# Lab_6.net
KiCad netlist of a schematic drawn in EAGLE
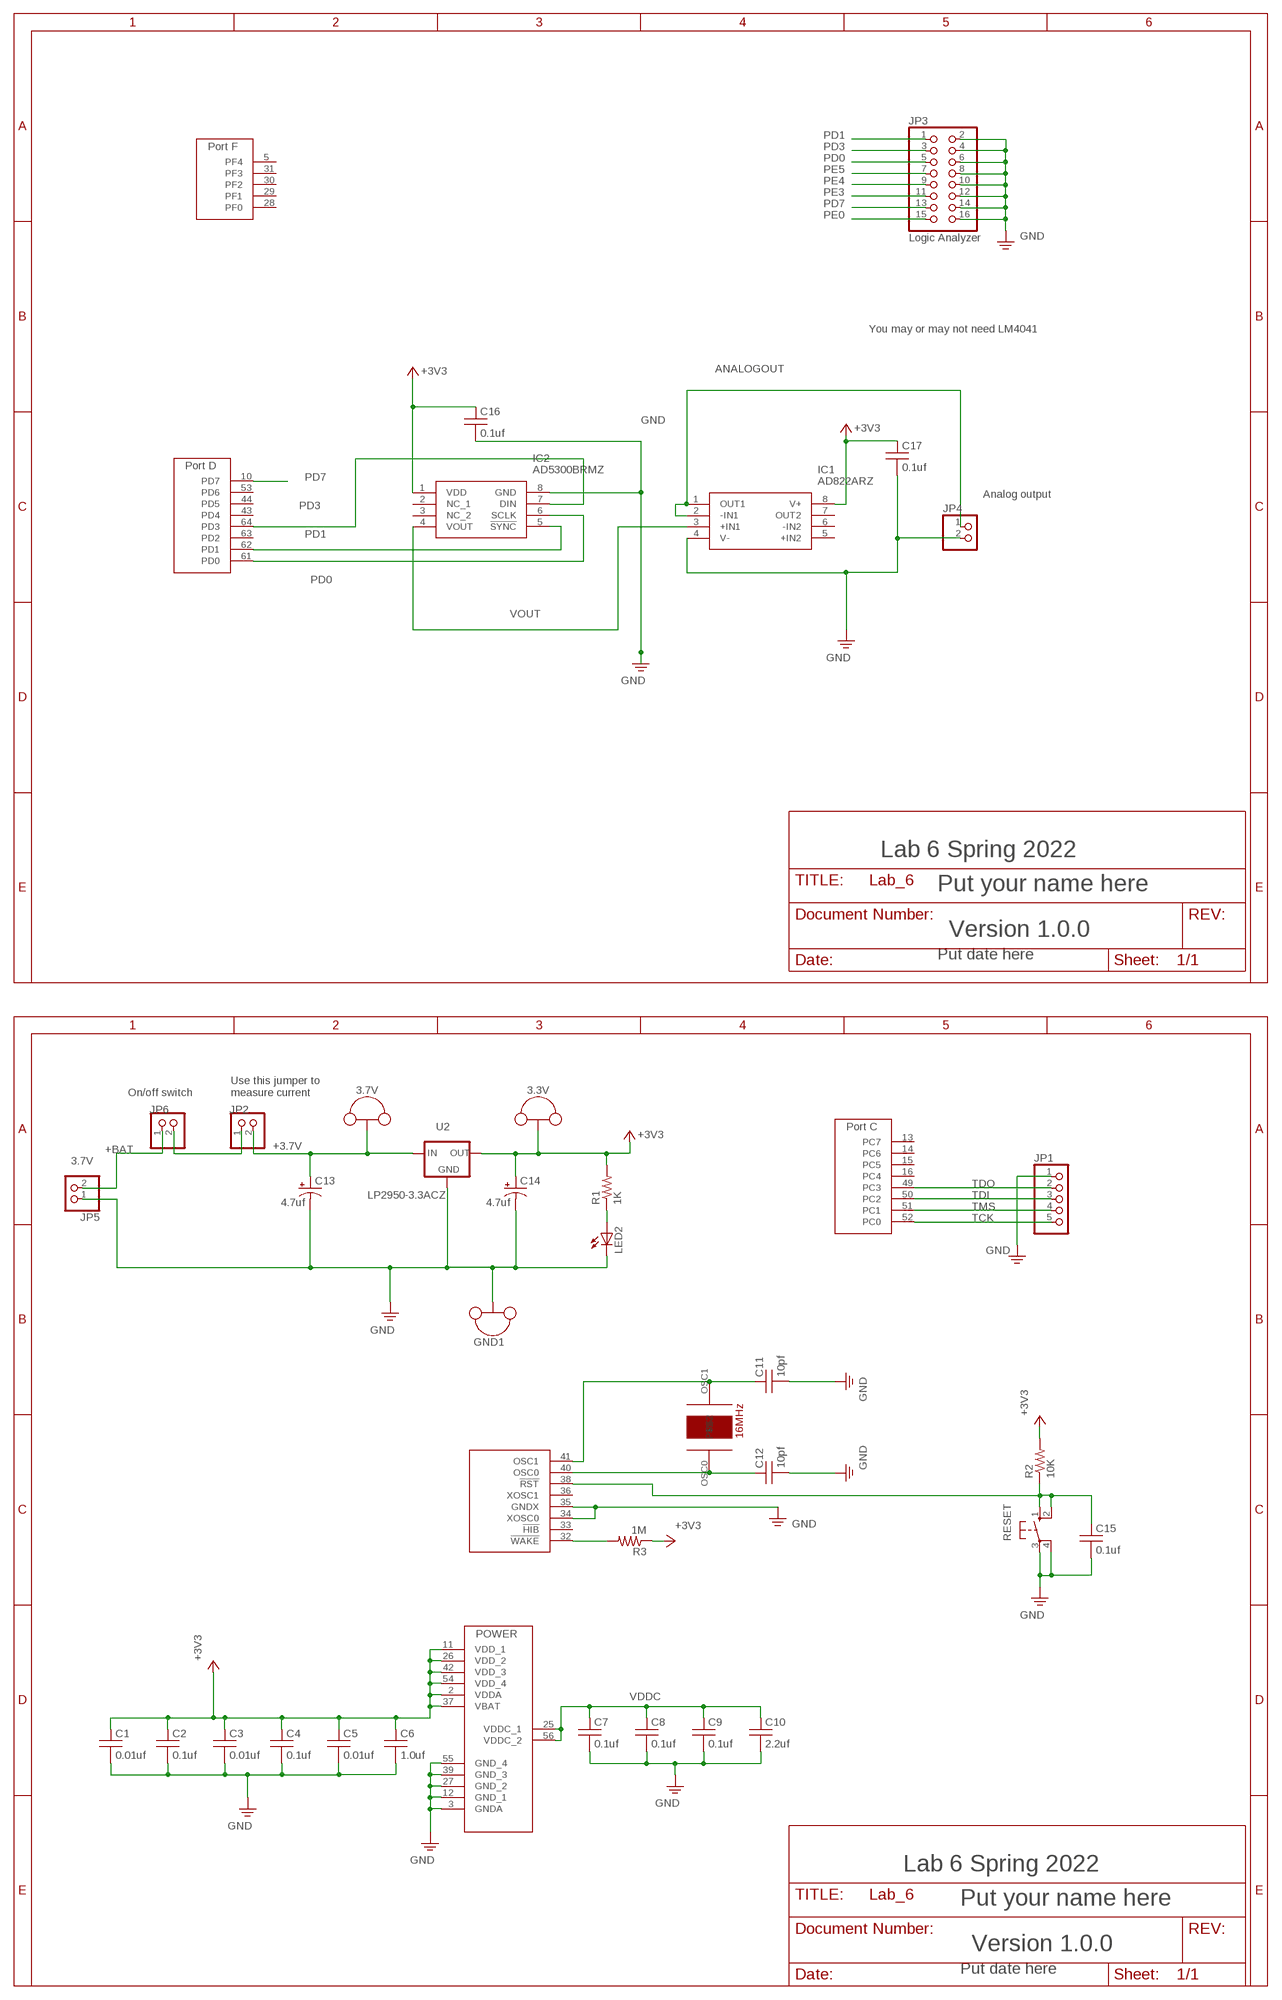
[diagram p0: schematic, sheet 1, part 1 of 2]
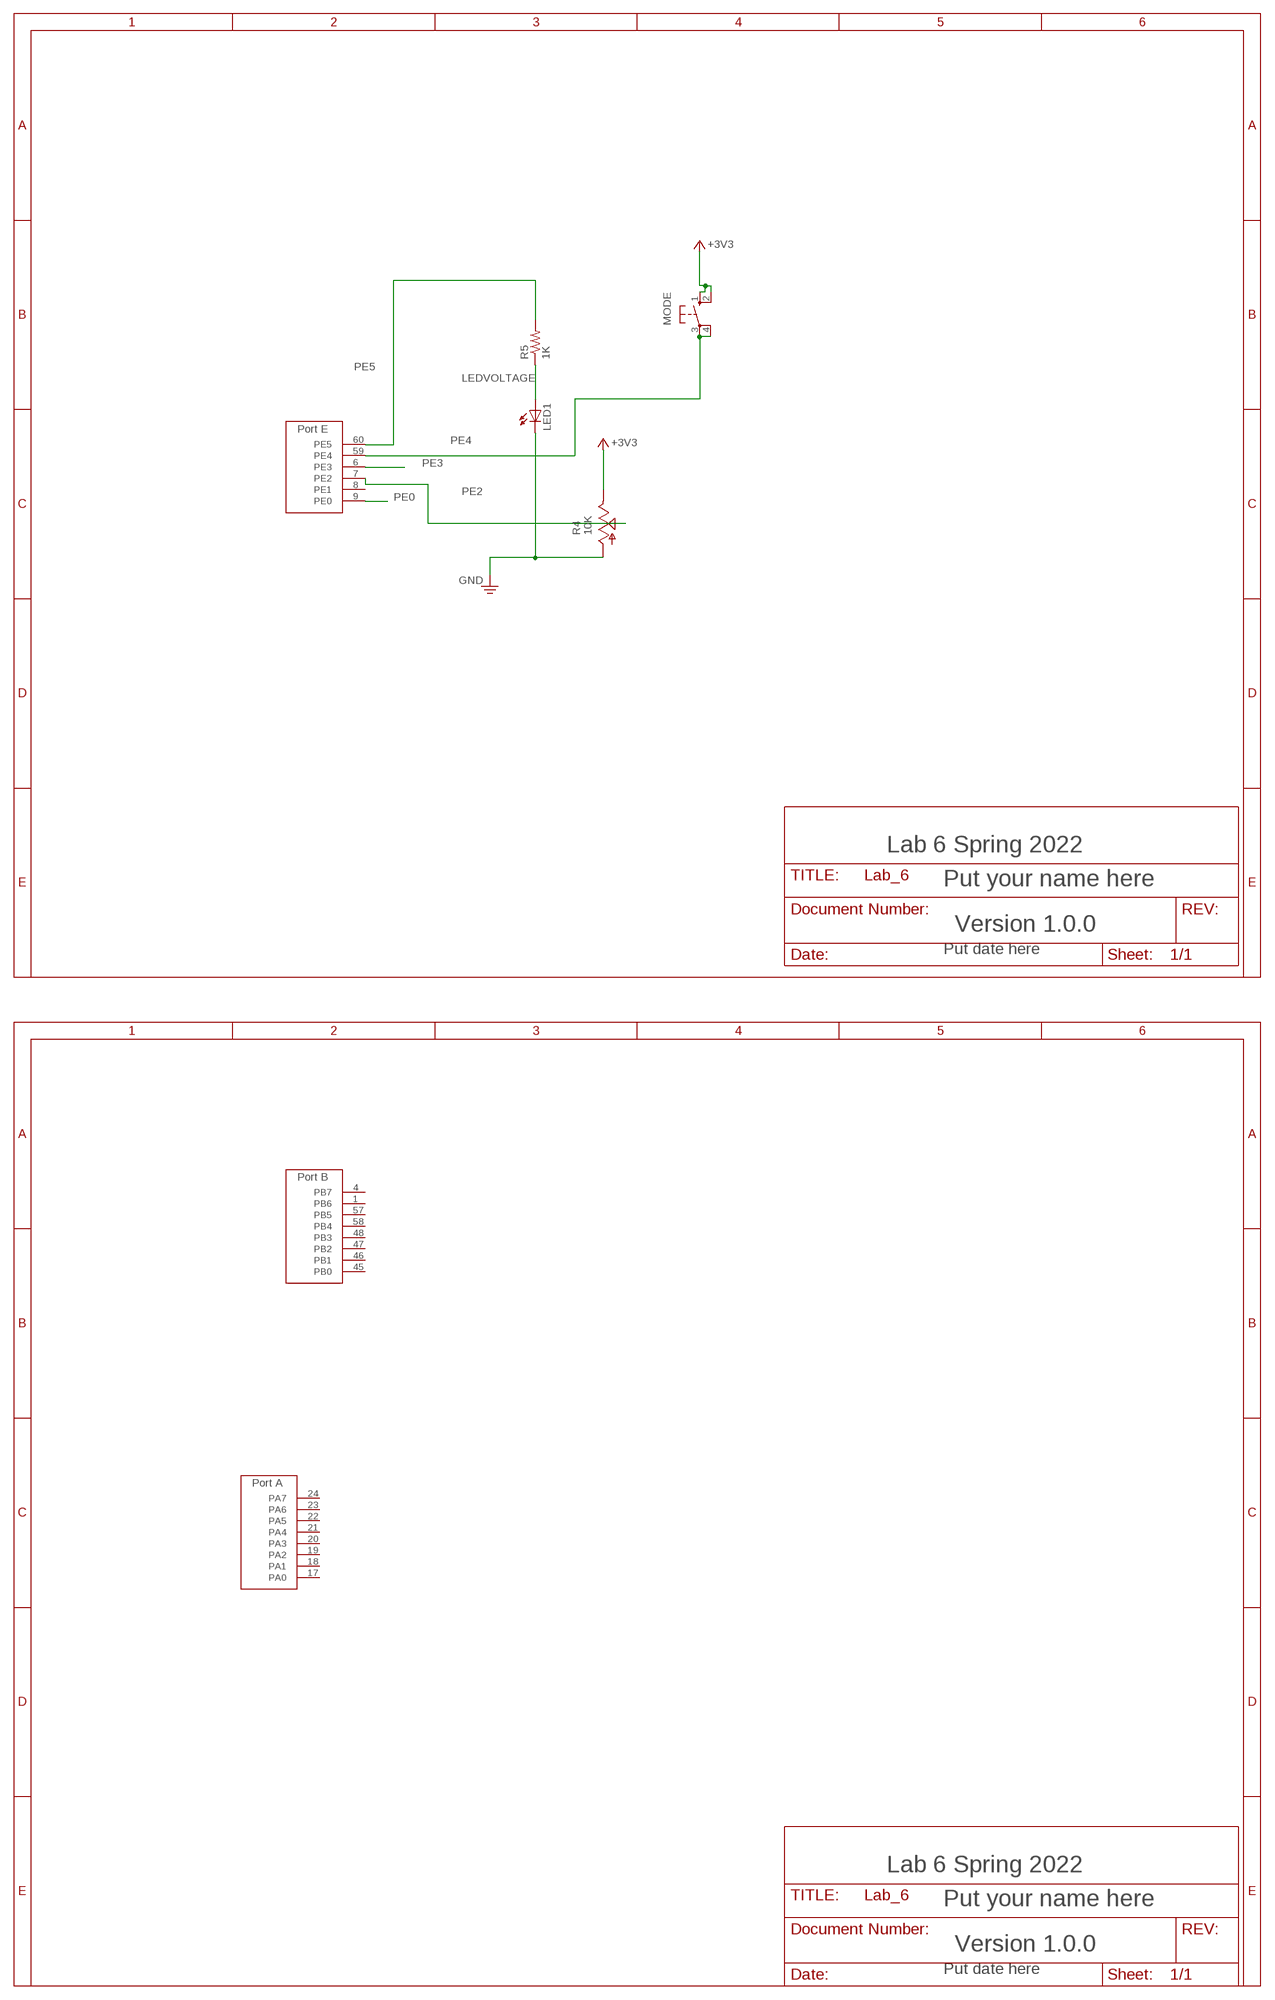
[diagram p1: schematic, sheet 1, part 2 of 2]

(export (version "E")
  (design (tool "Eeschema 10.0.6"))
  (components
    (comp (ref "3.3V")
      (value "TP_LOOP")
      (footprint "eagle-import:TP_LOOP")
      (libsource (lib "eagle-import") (part "TP_LOOP"))
    )
    (comp (ref "3.7V")
      (value "TP_LOOP")
      (footprint "eagle-import:TP_LOOP")
      (libsource (lib "eagle-import") (part "TP_LOOP"))
    )
    (comp (ref "C1")
      (value "0.01uf")
      (footprint "eagle-import:CAP100MIL")
      (libsource (lib "eagle-import") (part "CAPACITOR025-024X044"))
    )
    (comp (ref "C2")
      (value "0.1uf")
      (footprint "eagle-import:CAP100MIL")
      (libsource (lib "eagle-import") (part "CAPACITOR025-024X044"))
    )
    (comp (ref "C3")
      (value "0.01uf")
      (footprint "eagle-import:CAP100MIL")
      (libsource (lib "eagle-import") (part "CAPACITOR025-024X044"))
    )
    (comp (ref "C4")
      (value "0.1uf")
      (footprint "eagle-import:CAP100MIL")
      (libsource (lib "eagle-import") (part "CAPACITOR025-024X044"))
    )
    (comp (ref "C5")
      (value "0.01uf")
      (footprint "eagle-import:CAP100MIL")
      (libsource (lib "eagle-import") (part "CAPACITOR025-024X044"))
    )
    (comp (ref "C6")
      (value "1.0uf")
      (footprint "eagle-import:CAP100MIL")
      (libsource (lib "eagle-import") (part "CAPACITOR025-024X044"))
    )
    (comp (ref "C7")
      (value "0.1uf")
      (footprint "eagle-import:CAP100MIL")
      (libsource (lib "eagle-import") (part "CAPACITOR025-024X044"))
    )
    (comp (ref "C8")
      (value "0.1uf")
      (footprint "eagle-import:CAP100MIL")
      (libsource (lib "eagle-import") (part "CAPACITOR025-024X044"))
    )
    (comp (ref "C9")
      (value "0.1uf")
      (footprint "eagle-import:CAP100MIL")
      (libsource (lib "eagle-import") (part "CAPACITOR025-024X044"))
    )
    (comp (ref "C10")
      (value "2.2uf")
      (footprint "eagle-import:CAP100MIL")
      (libsource (lib "eagle-import") (part "CAPACITOR025-024X044"))
    )
    (comp (ref "C11")
      (value "10pf")
      (footprint "eagle-import:CAP100MIL")
      (libsource (lib "eagle-import") (part "CAPACITOR025-024X044"))
    )
    (comp (ref "C12")
      (value "10pf")
      (footprint "eagle-import:CAP100MIL")
      (libsource (lib "eagle-import") (part "CAPACITOR025-024X044"))
    )
    (comp (ref "C13")
      (value "4.7uf")
      (footprint "eagle-import:CAP200MILPOLARIZED")
      (libsource (lib "eagle-import") (part "CAPACITOR_POLARIZEDE5-6"))
    )
    (comp (ref "C14")
      (value "4.7uf")
      (footprint "eagle-import:CAP200MILPOLARIZED")
      (libsource (lib "eagle-import") (part "CAPACITOR_POLARIZEDE5-6"))
    )
    (comp (ref "C15")
      (value "0.1uf")
      (footprint "eagle-import:CAP100MIL")
      (libsource (lib "eagle-import") (part "CAPACITOR025-024X044"))
    )
    (comp (ref "C16")
      (value "0.1uf")
      (footprint "eagle-import:CAP100MIL")
      (libsource (lib "eagle-import") (part "CAPACITOR025-024X044"))
    )
    (comp (ref "C17")
      (value "0.1uf")
      (footprint "eagle-import:CAP100MIL")
      (libsource (lib "eagle-import") (part "CAPACITOR025-024X044"))
    )
    (comp (ref "GND1")
      (value "TP_LOOP")
      (footprint "eagle-import:TP_LOOP")
      (libsource (lib "eagle-import") (part "TP_LOOP"))
    )
    (comp (ref "IC1")
      (value "AD822ARZ")
      (footprint "eagle-import:SOIC127P600X175-8N")
      (fields (field (name "MOUSER2_PART_NUMBER") "584-AD822ARZ"))
      (libsource (lib "eagle-import") (part "AD822ARZ"))
    )
    (comp (ref "IC2")
      (value "AD5300BRMZ")
      (footprint "eagle-import:SOP65P490X110-8N")
      (fields (field (name "MOUSER_PART_NUMBER") "584-AD5300BRMZ"))
      (libsource (lib "eagle-import") (part "AD5300BRMZ"))
    )
    (comp (ref "JP1")
      (value "PINHD-1X5")
      (footprint "eagle-import:1X05")
      (libsource (lib "eagle-import") (part "PINHD-1X5"))
    )
    (comp (ref "JP2")
      (value "PINHD-1X2")
      (footprint "eagle-import:1X02")
      (libsource (lib "eagle-import") (part "PINHD-1X2"))
    )
    (comp (ref "JP3")
      (value "Logic Analyzer")
      (footprint "eagle-import:2X08")
      (libsource (lib "eagle-import") (part "PINHD-2X8"))
    )
    (comp (ref "JP4")
      (value "PINHD-1X2")
      (footprint "eagle-import:1X02")
      (libsource (lib "eagle-import") (part "PINHD-1X2"))
    )
    (comp (ref "JP5")
      (value "PINHD-1X2")
      (footprint "eagle-import:1X02")
      (libsource (lib "eagle-import") (part "PINHD-1X2"))
    )
    (comp (ref "JP6")
      (value "PINHD-1X2")
      (footprint "eagle-import:1X02")
      (libsource (lib "eagle-import") (part "PINHD-1X2"))
    )
    (comp (ref "LED1")
      (value "LED3MM")
      (footprint "eagle-import:LED3MM")
      (libsource (lib "eagle-import") (part "LED3MM"))
    )
    (comp (ref "LED2")
      (value "LED3MM")
      (footprint "eagle-import:LED3MM")
      (libsource (lib "eagle-import") (part "LED3MM"))
    )
    (comp (ref "MODE")
      (value "B3F-1052")
      (footprint "eagle-import:B3F-10XX")
      (fields (field (name "MPN") "B3F-1000"))
      (libsource (lib "eagle-import") (part "B3F-1052"))
    )
    (comp (ref "R1")
      (value "1K")
      (footprint "eagle-import:RES200MIL")
      (libsource (lib "eagle-import") (part "RESISTOR0204/5"))
    )
    (comp (ref "R2")
      (value "10K")
      (footprint "eagle-import:RES200MIL")
      (libsource (lib "eagle-import") (part "RESISTOR0204/5"))
    )
    (comp (ref "R3")
      (value "1M")
      (footprint "eagle-import:RES200MIL")
      (libsource (lib "eagle-import") (part "RESISTOR0204/5"))
    )
    (comp (ref "R4")
      (value "10K")
      (footprint "eagle-import:PTA2043")
      (libsource (lib "eagle-import") (part "POTENTIOMETER_PTA2043B25U"))
    )
    (comp (ref "R5")
      (value "1K")
      (footprint "eagle-import:RES200MIL")
      (libsource (lib "eagle-import") (part "RESISTOR0204/5"))
    )
    (comp (ref "RESET")
      (value "B3F-1052")
      (footprint "eagle-import:B3F-10XX")
      (fields (field (name "MPN") "B3F-1000"))
      (libsource (lib "eagle-import") (part "B3F-1052"))
    )
    (comp (ref "U1")
      (value "TM4C123GH6PM")
      (footprint "eagle-import:QFP50P1200X1200X160-64N")
      (libsource (lib "eagle-import") (part "TM4C123GH6PM"))
    )
    (comp (ref "U2")
      (value "LP2950-3.3ACZ")
      (footprint "eagle-import:TO92")
      (libsource (lib "eagle-import") (part "LP2950ACZ-3.3"))
    )
    (comp (ref "Y1")
      (value "16MHZ_CRYSTAL")
      (footprint "eagle-import:16MHZ_CRYSTAL")
      (libsource (lib "eagle-import") (part "16MHZ_CRYSTAL"))
    )
  )
  (nets
    (net (code "1") (name "+3V3") (class "Default")
      (node (ref "3.3V") (pin "P$1") (pinfunction "TP_P$1") (pintype "bidirectional"))
      (node (ref "3.3V") (pin "P$2") (pinfunction "TP_P$2") (pintype "bidirectional"))
      (node (ref "C1") (pin "1") (pinfunction "1_1") (pintype "passive"))
      (node (ref "C14") (pin "+") (pinfunction "+_+") (pintype "passive"))
      (node (ref "C16") (pin "1") (pinfunction "1_1") (pintype "passive"))
      (node (ref "C17") (pin "1") (pinfunction "1_1") (pintype "passive"))
      (node (ref "C2") (pin "1") (pinfunction "1_1") (pintype "passive"))
      (node (ref "C3") (pin "1") (pinfunction "1_1") (pintype "passive"))
      (node (ref "C4") (pin "1") (pinfunction "1_1") (pintype "passive"))
      (node (ref "C5") (pin "1") (pinfunction "1_1") (pintype "passive"))
      (node (ref "C6") (pin "1") (pinfunction "1_1") (pintype "passive"))
      (node (ref "IC1") (pin "8") (pinfunction "V+_8") (pintype "bidirectional"))
      (node (ref "IC2") (pin "1") (pinfunction "VDD_1") (pintype "bidirectional"))
      (node (ref "MODE") (pin "1") (pinfunction "S_1") (pintype "passive"))
      (node (ref "MODE") (pin "2") (pinfunction "S1_2") (pintype "passive"))
      (node (ref "R1") (pin "2") (pinfunction "2_2") (pintype "passive"))
      (node (ref "R2") (pin "2") (pinfunction "2_2") (pintype "passive"))
      (node (ref "R3") (pin "1") (pinfunction "1_1") (pintype "passive"))
      (node (ref "R4") (pin "1") (pinfunction "E_1") (pintype "passive"))
      (node (ref "U1") (pin "11") (pinfunction "VDD_1_11") (pintype "bidirectional"))
      (node (ref "U1") (pin "2") (pinfunction "VDDA_2") (pintype "bidirectional"))
      (node (ref "U1") (pin "26") (pinfunction "VDD_2_26") (pintype "bidirectional"))
      (node (ref "U1") (pin "37") (pinfunction "VBAT_37") (pintype "bidirectional"))
      (node (ref "U1") (pin "42") (pinfunction "VDD_3_42") (pintype "bidirectional"))
      (node (ref "U1") (pin "54") (pinfunction "VDD_4_54") (pintype "bidirectional"))
      (node (ref "U2") (pin "1") (pinfunction "OUT_1") (pintype "passive"))
    )
    (net (code "2") (name "/+3.7V") (class "Default")
      (node (ref "3.7V") (pin "P$1") (pinfunction "TP_P$1") (pintype "bidirectional"))
      (node (ref "3.7V") (pin "P$2") (pinfunction "TP_P$2") (pintype "bidirectional"))
      (node (ref "C13") (pin "+") (pinfunction "+_+") (pintype "passive"))
      (node (ref "JP2") (pin "2") (pinfunction "2_2") (pintype "passive"))
      (node (ref "U2") (pin "3") (pinfunction "IN_3") (pintype "input"))
    )
    (net (code "3") (name "/+BAT") (class "Default")
      (node (ref "JP5") (pin "2") (pinfunction "2_2") (pintype "passive"))
      (node (ref "JP6") (pin "1") (pinfunction "1_1") (pintype "passive"))
    )
    (net (code "4") (name "/ANALOGOUT") (class "Default")
      (node (ref "IC1") (pin "1") (pinfunction "OUT1_1") (pintype "bidirectional"))
      (node (ref "IC1") (pin "2") (pinfunction "-IN1_2") (pintype "bidirectional"))
      (node (ref "JP4") (pin "1") (pinfunction "1_1") (pintype "passive"))
    )
    (net (code "5") (name "/LEDVOLTAGE") (class "Default")
      (node (ref "LED1") (pin "A") (pinfunction "A_A") (pintype "passive"))
      (node (ref "R5") (pin "1") (pinfunction "1_1") (pintype "passive"))
    )
    (net (code "6") (name "/PD0") (class "Default")
      (node (ref "IC2") (pin "6") (pinfunction "SCLK_6") (pintype "bidirectional"))
      (node (ref "JP3") (pin "5") (pinfunction "5_5") (pintype "passive"))
      (node (ref "U1") (pin "61") (pinfunction "PD0_61") (pintype "bidirectional"))
    )
    (net (code "7") (name "/PD1") (class "Default")
      (node (ref "IC2") (pin "5") (pinfunction "~{SYNC}_5") (pintype "bidirectional"))
      (node (ref "JP3") (pin "1") (pinfunction "1_1") (pintype "passive"))
      (node (ref "U1") (pin "62") (pinfunction "PD1_62") (pintype "bidirectional"))
    )
    (net (code "8") (name "/PD3") (class "Default")
      (node (ref "IC2") (pin "7") (pinfunction "DIN_7") (pintype "bidirectional"))
      (node (ref "JP3") (pin "3") (pinfunction "3_3") (pintype "passive"))
      (node (ref "U1") (pin "64") (pinfunction "PD3_64") (pintype "bidirectional"))
    )
    (net (code "9") (name "/PD7") (class "Default")
      (node (ref "JP3") (pin "13") (pinfunction "13_13") (pintype "passive"))
      (node (ref "U1") (pin "10") (pinfunction "PD7_10") (pintype "bidirectional"))
    )
    (net (code "10") (name "/PE0") (class "Default")
      (node (ref "JP3") (pin "15") (pinfunction "15_15") (pintype "passive"))
      (node (ref "U1") (pin "9") (pinfunction "PE0_9") (pintype "bidirectional"))
    )
    (net (code "11") (name "/PE2") (class "Default")
      (node (ref "R4") (pin "2") (pinfunction "S_2") (pintype "passive"))
      (node (ref "U1") (pin "7") (pinfunction "PE2_7") (pintype "bidirectional"))
    )
    (net (code "12") (name "/PE3") (class "Default")
      (node (ref "JP3") (pin "11") (pinfunction "11_11") (pintype "passive"))
      (node (ref "U1") (pin "6") (pinfunction "PE3_6") (pintype "bidirectional"))
    )
    (net (code "13") (name "/PE4") (class "Default")
      (node (ref "JP3") (pin "9") (pinfunction "9_9") (pintype "passive"))
      (node (ref "MODE") (pin "3") (pinfunction "P_3") (pintype "passive"))
      (node (ref "MODE") (pin "4") (pinfunction "P1_4") (pintype "passive"))
      (node (ref "U1") (pin "59") (pinfunction "PE4_59") (pintype "bidirectional"))
    )
    (net (code "14") (name "/PE5") (class "Default")
      (node (ref "JP3") (pin "7") (pinfunction "7_7") (pintype "passive"))
      (node (ref "R5") (pin "2") (pinfunction "2_2") (pintype "passive"))
      (node (ref "U1") (pin "60") (pinfunction "PE5_60") (pintype "bidirectional"))
    )
    (net (code "15") (name "/TCK") (class "Default")
      (node (ref "JP1") (pin "5") (pinfunction "5_5") (pintype "passive"))
      (node (ref "U1") (pin "52") (pinfunction "PC0_52") (pintype "bidirectional"))
    )
    (net (code "16") (name "/TDI") (class "Default")
      (node (ref "JP1") (pin "3") (pinfunction "3_3") (pintype "passive"))
      (node (ref "U1") (pin "50") (pinfunction "PC2_50") (pintype "bidirectional"))
    )
    (net (code "17") (name "/TDO") (class "Default")
      (node (ref "JP1") (pin "2") (pinfunction "2_2") (pintype "passive"))
      (node (ref "U1") (pin "49") (pinfunction "PC3_49") (pintype "bidirectional"))
    )
    (net (code "18") (name "/TMS") (class "Default")
      (node (ref "JP1") (pin "4") (pinfunction "4_4") (pintype "passive"))
      (node (ref "U1") (pin "51") (pinfunction "PC1_51") (pintype "bidirectional"))
    )
    (net (code "19") (name "/VDDC") (class "Default")
      (node (ref "C10") (pin "1") (pinfunction "1_1") (pintype "passive"))
      (node (ref "C7") (pin "1") (pinfunction "1_1") (pintype "passive"))
      (node (ref "C8") (pin "1") (pinfunction "1_1") (pintype "passive"))
      (node (ref "C9") (pin "1") (pinfunction "1_1") (pintype "passive"))
      (node (ref "U1") (pin "25") (pinfunction "VDDC_1_25") (pintype "bidirectional"))
      (node (ref "U1") (pin "56") (pinfunction "VDDC_2_56") (pintype "bidirectional"))
    )
    (net (code "20") (name "/VOUT") (class "Default")
      (node (ref "IC1") (pin "3") (pinfunction "+IN1_3") (pintype "bidirectional"))
      (node (ref "IC2") (pin "4") (pinfunction "VOUT_4") (pintype "bidirectional"))
    )
    (net (code "21") (name "GND") (class "Default")
      (node (ref "C1") (pin "2") (pinfunction "2_2") (pintype "passive"))
      (node (ref "C10") (pin "2") (pinfunction "2_2") (pintype "passive"))
      (node (ref "C11") (pin "2") (pinfunction "2_2") (pintype "passive"))
      (node (ref "C12") (pin "2") (pinfunction "2_2") (pintype "passive"))
      (node (ref "C13") (pin "-") (pinfunction "-_-") (pintype "passive"))
      (node (ref "C14") (pin "-") (pinfunction "-_-") (pintype "passive"))
      (node (ref "C15") (pin "2") (pinfunction "2_2") (pintype "passive"))
      (node (ref "C16") (pin "2") (pinfunction "2_2") (pintype "passive"))
      (node (ref "C17") (pin "2") (pinfunction "2_2") (pintype "passive"))
      (node (ref "C2") (pin "2") (pinfunction "2_2") (pintype "passive"))
      (node (ref "C3") (pin "2") (pinfunction "2_2") (pintype "passive"))
      (node (ref "C4") (pin "2") (pinfunction "2_2") (pintype "passive"))
      (node (ref "C5") (pin "2") (pinfunction "2_2") (pintype "passive"))
      (node (ref "C6") (pin "2") (pinfunction "2_2") (pintype "passive"))
      (node (ref "C7") (pin "2") (pinfunction "2_2") (pintype "passive"))
      (node (ref "C8") (pin "2") (pinfunction "2_2") (pintype "passive"))
      (node (ref "C9") (pin "2") (pinfunction "2_2") (pintype "passive"))
      (node (ref "GND1") (pin "P$1") (pinfunction "TP_P$1") (pintype "bidirectional"))
      (node (ref "GND1") (pin "P$2") (pinfunction "TP_P$2") (pintype "bidirectional"))
      (node (ref "IC1") (pin "4") (pinfunction "V-_4") (pintype "bidirectional"))
      (node (ref "IC2") (pin "8") (pinfunction "GND_8") (pintype "bidirectional"))
      (node (ref "JP1") (pin "1") (pinfunction "1_1") (pintype "passive"))
      (node (ref "JP3") (pin "10") (pinfunction "10_10") (pintype "passive"))
      (node (ref "JP3") (pin "12") (pinfunction "12_12") (pintype "passive"))
      (node (ref "JP3") (pin "14") (pinfunction "14_14") (pintype "passive"))
      (node (ref "JP3") (pin "16") (pinfunction "16_16") (pintype "passive"))
      (node (ref "JP3") (pin "2") (pinfunction "2_2") (pintype "passive"))
      (node (ref "JP3") (pin "4") (pinfunction "4_4") (pintype "passive"))
      (node (ref "JP3") (pin "6") (pinfunction "6_6") (pintype "passive"))
      (node (ref "JP3") (pin "8") (pinfunction "8_8") (pintype "passive"))
      (node (ref "JP4") (pin "2") (pinfunction "2_2") (pintype "passive"))
      (node (ref "JP5") (pin "1") (pinfunction "1_1") (pintype "passive"))
      (node (ref "LED1") (pin "K") (pinfunction "C_K") (pintype "passive"))
      (node (ref "LED2") (pin "K") (pinfunction "C_K") (pintype "passive"))
      (node (ref "R4") (pin "3") (pinfunction "A_3") (pintype "passive"))
      (node (ref "RESET") (pin "3") (pinfunction "P_3") (pintype "passive"))
      (node (ref "RESET") (pin "4") (pinfunction "P1_4") (pintype "passive"))
      (node (ref "U1") (pin "12") (pinfunction "GND_1_12") (pintype "bidirectional"))
      (node (ref "U1") (pin "27") (pinfunction "GND_2_27") (pintype "bidirectional"))
      (node (ref "U1") (pin "3") (pinfunction "GNDA_3") (pintype "bidirectional"))
      (node (ref "U1") (pin "34") (pinfunction "XOSC0_34") (pintype "bidirectional"))
      (node (ref "U1") (pin "35") (pinfunction "GNDX_35") (pintype "bidirectional"))
      (node (ref "U1") (pin "39") (pinfunction "GND_3_39") (pintype "bidirectional"))
      (node (ref "U1") (pin "55") (pinfunction "GND_4_55") (pintype "bidirectional"))
      (node (ref "U2") (pin "2") (pinfunction "GND_2") (pintype "input"))
    )
    (net (code "22") (name "Net-(JP2-Pad1)") (class "Default")
      (node (ref "JP2") (pin "1") (pinfunction "1_1") (pintype "passive"))
      (node (ref "JP6") (pin "2") (pinfunction "2_2") (pintype "passive"))
    )
    (net (code "23") (name "Net-(LED2-PadA)") (class "Default")
      (node (ref "LED2") (pin "A") (pinfunction "A_A") (pintype "passive"))
      (node (ref "R1") (pin "1") (pinfunction "1_1") (pintype "passive"))
    )
    (net (code "24") (name "Net-(RESET-S)") (class "Default")
      (node (ref "C15") (pin "1") (pinfunction "1_1") (pintype "passive"))
      (node (ref "R2") (pin "1") (pinfunction "1_1") (pintype "passive"))
      (node (ref "RESET") (pin "1") (pinfunction "S_1") (pintype "passive"))
      (node (ref "RESET") (pin "2") (pinfunction "S1_2") (pintype "passive"))
      (node (ref "U1") (pin "38") (pinfunction "~{RST}_38") (pintype "bidirectional"))
    )
    (net (code "25") (name "Net-(U1G-OSC0)") (class "Default")
      (node (ref "C12") (pin "1") (pinfunction "1_1") (pintype "passive"))
      (node (ref "U1") (pin "40") (pinfunction "OSC0_40") (pintype "bidirectional"))
      (node (ref "Y1") (pin "OSC0") (pinfunction "P$1_OSC0") (pintype "bidirectional"))
    )
    (net (code "26") (name "Net-(U1G-OSC1)") (class "Default")
      (node (ref "C11") (pin "1") (pinfunction "1_1") (pintype "passive"))
      (node (ref "U1") (pin "41") (pinfunction "OSC1_41") (pintype "bidirectional"))
      (node (ref "Y1") (pin "OSC1") (pinfunction "P$2_OSC1") (pintype "bidirectional"))
    )
    (net (code "27") (name "Net-(U1G-~{WAKE})") (class "Default")
      (node (ref "R3") (pin "2") (pinfunction "2_2") (pintype "passive"))
      (node (ref "U1") (pin "32") (pinfunction "~{WAKE}_32") (pintype "bidirectional"))
    )
    (net (code "28") (name "unconnected-(IC1-+IN2-Pad5)") (class "Default")
      (node (ref "IC1") (pin "5") (pinfunction "+IN2_5") (pintype "bidirectional"))
    )
    (net (code "29") (name "unconnected-(IC1--IN2-Pad6)") (class "Default")
      (node (ref "IC1") (pin "6") (pinfunction "-IN2_6") (pintype "bidirectional"))
    )
    (net (code "30") (name "unconnected-(IC1-OUT2-Pad7)") (class "Default")
      (node (ref "IC1") (pin "7") (pinfunction "OUT2_7") (pintype "bidirectional"))
    )
    (net (code "31") (name "unconnected-(IC2-NC_1-Pad2)") (class "Default")
      (node (ref "IC2") (pin "2") (pinfunction "NC_1_2") (pintype "bidirectional"))
    )
    (net (code "32") (name "unconnected-(IC2-NC_2-Pad3)") (class "Default")
      (node (ref "IC2") (pin "3") (pinfunction "NC_2_3") (pintype "bidirectional"))
    )
    (net (code "33") (name "unconnected-(U1A-PA0-Pad17)") (class "Default")
      (node (ref "U1") (pin "17") (pinfunction "PA0_17") (pintype "bidirectional"))
    )
    (net (code "34") (name "unconnected-(U1A-PA1-Pad18)") (class "Default")
      (node (ref "U1") (pin "18") (pinfunction "PA1_18") (pintype "bidirectional"))
    )
    (net (code "35") (name "unconnected-(U1A-PA2-Pad19)") (class "Default")
      (node (ref "U1") (pin "19") (pinfunction "PA2_19") (pintype "bidirectional"))
    )
    (net (code "36") (name "unconnected-(U1A-PA3-Pad20)") (class "Default")
      (node (ref "U1") (pin "20") (pinfunction "PA3_20") (pintype "bidirectional"))
    )
    (net (code "37") (name "unconnected-(U1A-PA4-Pad21)") (class "Default")
      (node (ref "U1") (pin "21") (pinfunction "PA4_21") (pintype "bidirectional"))
    )
    (net (code "38") (name "unconnected-(U1A-PA5-Pad22)") (class "Default")
      (node (ref "U1") (pin "22") (pinfunction "PA5_22") (pintype "bidirectional"))
    )
    (net (code "39") (name "unconnected-(U1A-PA6-Pad23)") (class "Default")
      (node (ref "U1") (pin "23") (pinfunction "PA6_23") (pintype "bidirectional"))
    )
    (net (code "40") (name "unconnected-(U1A-PA7-Pad24)") (class "Default")
      (node (ref "U1") (pin "24") (pinfunction "PA7_24") (pintype "bidirectional"))
    )
    (net (code "41") (name "unconnected-(U1B-PB0-Pad45)") (class "Default")
      (node (ref "U1") (pin "45") (pinfunction "PB0_45") (pintype "bidirectional"))
    )
    (net (code "42") (name "unconnected-(U1B-PB1-Pad46)") (class "Default")
      (node (ref "U1") (pin "46") (pinfunction "PB1_46") (pintype "bidirectional"))
    )
    (net (code "43") (name "unconnected-(U1B-PB2-Pad47)") (class "Default")
      (node (ref "U1") (pin "47") (pinfunction "PB2_47") (pintype "bidirectional"))
    )
    (net (code "44") (name "unconnected-(U1B-PB3-Pad48)") (class "Default")
      (node (ref "U1") (pin "48") (pinfunction "PB3_48") (pintype "bidirectional"))
    )
    (net (code "45") (name "unconnected-(U1B-PB4-Pad58)") (class "Default")
      (node (ref "U1") (pin "58") (pinfunction "PB4_58") (pintype "bidirectional"))
    )
    (net (code "46") (name "unconnected-(U1B-PB5-Pad57)") (class "Default")
      (node (ref "U1") (pin "57") (pinfunction "PB5_57") (pintype "bidirectional"))
    )
    (net (code "47") (name "unconnected-(U1B-PB6-Pad1)") (class "Default")
      (node (ref "U1") (pin "1") (pinfunction "PB6_1") (pintype "bidirectional"))
    )
    (net (code "48") (name "unconnected-(U1B-PB7-Pad4)") (class "Default")
      (node (ref "U1") (pin "4") (pinfunction "PB7_4") (pintype "bidirectional"))
    )
    (net (code "49") (name "unconnected-(U1C-PC4-Pad16)") (class "Default")
      (node (ref "U1") (pin "16") (pinfunction "PC4_16") (pintype "bidirectional"))
    )
    (net (code "50") (name "unconnected-(U1C-PC5-Pad15)") (class "Default")
      (node (ref "U1") (pin "15") (pinfunction "PC5_15") (pintype "bidirectional"))
    )
    (net (code "51") (name "unconnected-(U1C-PC6-Pad14)") (class "Default")
      (node (ref "U1") (pin "14") (pinfunction "PC6_14") (pintype "bidirectional"))
    )
    (net (code "52") (name "unconnected-(U1C-PC7-Pad13)") (class "Default")
      (node (ref "U1") (pin "13") (pinfunction "PC7_13") (pintype "bidirectional"))
    )
    (net (code "53") (name "unconnected-(U1D-PD2-Pad63)") (class "Default")
      (node (ref "U1") (pin "63") (pinfunction "PD2_63") (pintype "bidirectional"))
    )
    (net (code "54") (name "unconnected-(U1D-PD4-Pad43)") (class "Default")
      (node (ref "U1") (pin "43") (pinfunction "PD4_43") (pintype "bidirectional"))
    )
    (net (code "55") (name "unconnected-(U1D-PD5-Pad44)") (class "Default")
      (node (ref "U1") (pin "44") (pinfunction "PD5_44") (pintype "bidirectional"))
    )
    (net (code "56") (name "unconnected-(U1D-PD6-Pad53)") (class "Default")
      (node (ref "U1") (pin "53") (pinfunction "PD6_53") (pintype "bidirectional"))
    )
    (net (code "57") (name "unconnected-(U1E-PE1-Pad8)") (class "Default")
      (node (ref "U1") (pin "8") (pinfunction "PE1_8") (pintype "bidirectional"))
    )
    (net (code "58") (name "unconnected-(U1F-PF0-Pad28)") (class "Default")
      (node (ref "U1") (pin "28") (pinfunction "PF0_28") (pintype "bidirectional"))
    )
    (net (code "59") (name "unconnected-(U1F-PF1-Pad29)") (class "Default")
      (node (ref "U1") (pin "29") (pinfunction "PF1_29") (pintype "bidirectional"))
    )
    (net (code "60") (name "unconnected-(U1F-PF2-Pad30)") (class "Default")
      (node (ref "U1") (pin "30") (pinfunction "PF2_30") (pintype "bidirectional"))
    )
    (net (code "61") (name "unconnected-(U1F-PF3-Pad31)") (class "Default")
      (node (ref "U1") (pin "31") (pinfunction "PF3_31") (pintype "bidirectional"))
    )
    (net (code "62") (name "unconnected-(U1F-PF4-Pad5)") (class "Default")
      (node (ref "U1") (pin "5") (pinfunction "PF4_5") (pintype "bidirectional"))
    )
    (net (code "63") (name "unconnected-(U1G-XOSC1-Pad36)") (class "Default")
      (node (ref "U1") (pin "36") (pinfunction "XOSC1_36") (pintype "bidirectional"))
    )
    (net (code "64") (name "unconnected-(U1G-~{HIB}-Pad33)") (class "Default")
      (node (ref "U1") (pin "33") (pinfunction "~{HIB}_33") (pintype "bidirectional"))
    )
  )
)
